# Kajtu_-DSP_user_interface.net
KiCad netlist of a schematic drawn in Altium Designer
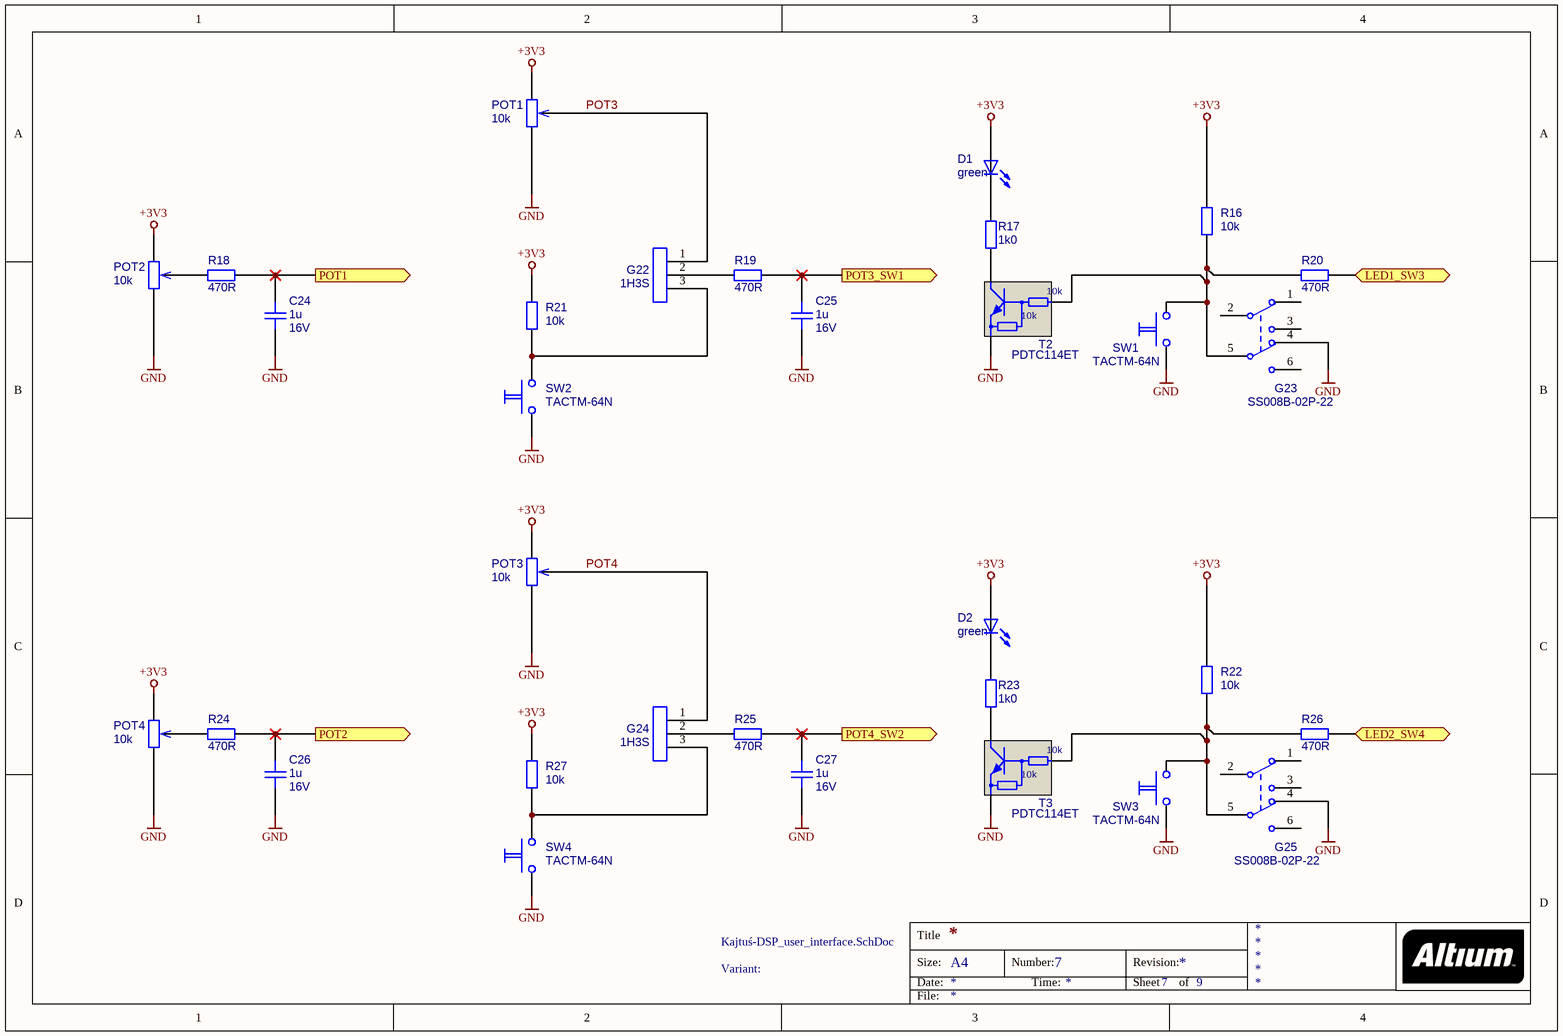
[diagram p0: Kajtuś-DSP_user_interface.SchDoc]

(export (version "E")
  (design (tool "Eeschema 10.0.6"))
  (components
    (comp (ref "C24")
      (value "1u")
      (footprint "C_0603_MA")
      (description "Kondensator ceramiczny SMD")
      (fields (field (name "PART NUMBER") "C_0603_1u_16V_X5R") (field (name "VOLTAGE") "16V"))
      (libsource (lib "AD_ostry_intlib") (part "C_0603_1u_16V_X5R"))
    )
    (comp (ref "C25")
      (value "1u")
      (footprint "C_0603_MA")
      (description "Kondensator ceramiczny SMD")
      (fields (field (name "PART NUMBER") "C_0603_1u_16V_X5R") (field (name "VOLTAGE") "16V"))
      (libsource (lib "AD_ostry_intlib") (part "C_0603_1u_16V_X5R"))
    )
    (comp (ref "C26")
      (value "1u")
      (footprint "C_0603_MA")
      (description "Kondensator ceramiczny SMD")
      (fields (field (name "PART NUMBER") "C_0603_1u_16V_X5R") (field (name "VOLTAGE") "16V"))
      (libsource (lib "AD_ostry_intlib") (part "C_0603_1u_16V_X5R"))
    )
    (comp (ref "C27")
      (value "1u")
      (footprint "C_0603_MA")
      (description "Kondensator ceramiczny SMD")
      (fields (field (name "PART NUMBER") "C_0603_1u_16V_X5R") (field (name "VOLTAGE") "16V"))
      (libsource (lib "AD_ostry_intlib") (part "C_0603_1u_16V_X5R"))
    )
    (comp (ref "D1")
      (value "green")
      (footprint "LED_0805_G")
      (description "Dioda LED SMD")
      (fields (field (name "PART NUMBER") "LED_SMD_generic") (field (name "MANUFACTURER") "??"))
      (libsource (lib "AD_ostry_intlib") (part "LED_SMD_generic"))
    )
    (comp (ref "D2")
      (value "green")
      (footprint "LED_0805_G")
      (description "Dioda LED SMD")
      (fields (field (name "PART NUMBER") "LED_SMD_generic") (field (name "MANUFACTURER") "??"))
      (libsource (lib "AD_ostry_intlib") (part "LED_SMD_generic"))
    )
    (comp (ref "G22")
      (value "1H3S")
      (footprint "1H3S_FHS")
      (description "Listwa jednorzędowa, 1x3 piny, raster 2,54mm")
      (fields (field (name "PART NUMBER") "G_1H3S") (field (name "MANUFACTURER") "generic"))
      (libsource (lib "AD_ostry_intlib") (part "G_1H3S"))
    )
    (comp (ref "G23")
      (value "SS008B-02P-22")
      (footprint "SW_DPDT_SS008B-02P-22")
      (description "Przełącznik suwakowy, DPTD")
      (fields
        (field (name "PART NUMBER") "SW_DPDT_SS008B-02P-22")
        (field (name "MANUFACTURER") "Canal Electronic")
      )
      (libsource (lib "AD_ostry_intlib") (part "SW_DPDT_SS008B-02P-22"))
    )
    (comp (ref "G24")
      (value "1H3S")
      (footprint "1H3S_FHS")
      (description "Listwa jednorzędowa, 1x3 piny, raster 2,54mm")
      (fields (field (name "PART NUMBER") "G_1H3S") (field (name "MANUFACTURER") "generic"))
      (libsource (lib "AD_ostry_intlib") (part "G_1H3S"))
    )
    (comp (ref "G25")
      (value "SS008B-02P-22")
      (footprint "SW_DPDT_SS008B-02P-22")
      (description "Przełącznik suwakowy, DPTD")
      (fields
        (field (name "PART NUMBER") "SW_DPDT_SS008B-02P-22")
        (field (name "MANUFACTURER") "Canal Electronic")
      )
      (libsource (lib "AD_ostry_intlib") (part "SW_DPDT_SS008B-02P-22"))
    )
    (comp (ref "POT1")
      (value "10k")
      (footprint "POT_BOURNS_3362P")
      (description "Potencjometr")
      (fields (field (name "PART NUMBER") "??") (field (name "MANUFACTURER") "bOURNS"))
      (libsource (lib "AD_ostry_intlib") (part "POT_10k_BOURNS_3362P"))
    )
    (comp (ref "POT2")
      (value "10k")
      (footprint "POT_BOURNS_3362P")
      (description "Potencjometr")
      (fields (field (name "PART NUMBER") "??") (field (name "MANUFACTURER") "bOURNS"))
      (libsource (lib "AD_ostry_intlib") (part "POT_10k_BOURNS_3362P"))
    )
    (comp (ref "POT3")
      (value "10k")
      (footprint "POT_BOURNS_3362P")
      (description "Potencjometr")
      (fields (field (name "PART NUMBER") "??") (field (name "MANUFACTURER") "bOURNS"))
      (libsource (lib "AD_ostry_intlib") (part "POT_10k_BOURNS_3362P"))
    )
    (comp (ref "POT4")
      (value "10k")
      (footprint "POT_BOURNS_3362P")
      (description "Potencjometr")
      (fields (field (name "PART NUMBER") "??") (field (name "MANUFACTURER") "bOURNS"))
      (libsource (lib "AD_ostry_intlib") (part "POT_10k_BOURNS_3362P"))
    )
    (comp (ref "R16")
      (value "10k")
      (footprint "R_0603_MA")
      (description "Rezystor SMD")
      (fields (field (name "MANUFACTURER") "Royal Ohm") (field (name "PART NUMBER") "R_0603_10k_5%"))
      (libsource (lib "AD_ostry_intlib") (part "R_0603_10k_5%"))
    )
    (comp (ref "R17")
      (value "1k0")
      (footprint "R_0603_MA")
      (description "Rezystor SMD")
      (fields (field (name "MANUFACTURER") "Royal Ohm") (field (name "PART NUMBER") "R_0603_1k0_5%"))
      (libsource (lib "AD_ostry_intlib") (part "R_0603_1k0_5%"))
    )
    (comp (ref "R18")
      (value "470R")
      (footprint "R_0603_MA")
      (description "Rezystor SMD")
      (fields (field (name "PART NUMBER") "R_0603_470R_5%") (field (name "MANUFACTURER") "Royal Ohm"))
      (libsource (lib "AD_ostry_intlib") (part "R_0603_470R_5%"))
    )
    (comp (ref "R19")
      (value "470R")
      (footprint "R_0603_MA")
      (description "Rezystor SMD")
      (fields (field (name "PART NUMBER") "R_0603_470R_5%") (field (name "MANUFACTURER") "Royal Ohm"))
      (libsource (lib "AD_ostry_intlib") (part "R_0603_470R_5%"))
    )
    (comp (ref "R20")
      (value "470R")
      (footprint "R_0603_MA")
      (description "Rezystor SMD")
      (fields (field (name "PART NUMBER") "R_0603_470R_5%") (field (name "MANUFACTURER") "Royal Ohm"))
      (libsource (lib "AD_ostry_intlib") (part "R_0603_470R_5%"))
    )
    (comp (ref "R21")
      (value "10k")
      (footprint "R_0603_MA")
      (description "Rezystor SMD")
      (fields (field (name "MANUFACTURER") "Royal Ohm") (field (name "PART NUMBER") "R_0603_10k_5%"))
      (libsource (lib "AD_ostry_intlib") (part "R_0603_10k_5%"))
    )
    (comp (ref "R22")
      (value "10k")
      (footprint "R_0603_MA")
      (description "Rezystor SMD")
      (fields (field (name "MANUFACTURER") "Royal Ohm") (field (name "PART NUMBER") "R_0603_10k_5%"))
      (libsource (lib "AD_ostry_intlib") (part "R_0603_10k_5%"))
    )
    (comp (ref "R23")
      (value "1k0")
      (footprint "R_0603_MA")
      (description "Rezystor SMD")
      (fields (field (name "MANUFACTURER") "Royal Ohm") (field (name "PART NUMBER") "R_0603_1k0_5%"))
      (libsource (lib "AD_ostry_intlib") (part "R_0603_1k0_5%"))
    )
    (comp (ref "R24")
      (value "470R")
      (footprint "R_0603_MA")
      (description "Rezystor SMD")
      (fields (field (name "PART NUMBER") "R_0603_470R_5%") (field (name "MANUFACTURER") "Royal Ohm"))
      (libsource (lib "AD_ostry_intlib") (part "R_0603_470R_5%"))
    )
    (comp (ref "R25")
      (value "470R")
      (footprint "R_0603_MA")
      (description "Rezystor SMD")
      (fields (field (name "PART NUMBER") "R_0603_470R_5%") (field (name "MANUFACTURER") "Royal Ohm"))
      (libsource (lib "AD_ostry_intlib") (part "R_0603_470R_5%"))
    )
    (comp (ref "R26")
      (value "470R")
      (footprint "R_0603_MA")
      (description "Rezystor SMD")
      (fields (field (name "PART NUMBER") "R_0603_470R_5%") (field (name "MANUFACTURER") "Royal Ohm"))
      (libsource (lib "AD_ostry_intlib") (part "R_0603_470R_5%"))
    )
    (comp (ref "R27")
      (value "10k")
      (footprint "R_0603_MA")
      (description "Rezystor SMD")
      (fields (field (name "MANUFACTURER") "Royal Ohm") (field (name "PART NUMBER") "R_0603_10k_5%"))
      (libsource (lib "AD_ostry_intlib") (part "R_0603_10k_5%"))
    )
    (comp (ref "SW1")
      (value "TACTM-64N")
      (footprint "SW_TACTM-64N")
      (description "Microswitch")
      (fields (field (name "PART NUMBER") "SW_TACTM-64N") (field (name "MANUFACTURER") "Ninigi"))
      (libsource (lib "AD_ostry_intlib") (part "SW_TACTM-64N"))
    )
    (comp (ref "SW2")
      (value "TACTM-64N")
      (footprint "SW_TACTM-64N")
      (description "Microswitch")
      (fields (field (name "PART NUMBER") "SW_TACTM-64N") (field (name "MANUFACTURER") "Ninigi"))
      (libsource (lib "AD_ostry_intlib") (part "SW_TACTM-64N"))
    )
    (comp (ref "SW3")
      (value "TACTM-64N")
      (footprint "SW_TACTM-64N")
      (description "Microswitch")
      (fields (field (name "PART NUMBER") "SW_TACTM-64N") (field (name "MANUFACTURER") "Ninigi"))
      (libsource (lib "AD_ostry_intlib") (part "SW_TACTM-64N"))
    )
    (comp (ref "SW4")
      (value "TACTM-64N")
      (footprint "SW_TACTM-64N")
      (description "Microswitch")
      (fields (field (name "PART NUMBER") "SW_TACTM-64N") (field (name "MANUFACTURER") "Ninigi"))
      (libsource (lib "AD_ostry_intlib") (part "SW_TACTM-64N"))
    )
    (comp (ref "T2")
      (value "PDTC114ET")
      (footprint "SOT-23")
      (description "NPN resistor-equipped transistor; R1=10k, R2=10k")
      (libsource (lib "MM_transistors") (part "T_SOT-23_PDTC114ET"))
    )
    (comp (ref "T3")
      (value "PDTC114ET")
      (footprint "SOT-23")
      (description "NPN resistor-equipped transistor; R1=10k, R2=10k")
      (libsource (lib "MM_transistors") (part "T_SOT-23_PDTC114ET"))
    )
  )
  (nets
    (net (code "1") (name "+3V3") (class "Default")
      (node (ref "D1") (pin "1") (pinfunction "A_1") (pintype "passive"))
      (node (ref "D2") (pin "1") (pinfunction "A_1") (pintype "passive"))
      (node (ref "POT1") (pin "1") (pinfunction "1_1") (pintype "passive"))
      (node (ref "POT2") (pin "1") (pinfunction "1_1") (pintype "passive"))
      (node (ref "POT3") (pin "1") (pinfunction "1_1") (pintype "passive"))
      (node (ref "POT4") (pin "1") (pinfunction "1_1") (pintype "passive"))
      (node (ref "R16") (pin "1") (pinfunction "1_1") (pintype "passive"))
      (node (ref "R21") (pin "1") (pinfunction "1_1") (pintype "passive"))
      (node (ref "R22") (pin "1") (pinfunction "1_1") (pintype "passive"))
      (node (ref "R27") (pin "1") (pinfunction "1_1") (pintype "passive"))
    )
    (net (code "2") (name "/LED1_SW3") (class "Default")
      (node (ref "R20") (pin "2") (pinfunction "2_2") (pintype "passive"))
    )
    (net (code "3") (name "/LED2_SW4") (class "Default")
      (node (ref "R26") (pin "2") (pinfunction "2_2") (pintype "passive"))
    )
    (net (code "4") (name "/POT1") (class "Default")
      (node (ref "C24") (pin "1") (pinfunction "1_1") (pintype "passive"))
      (node (ref "R18") (pin "2") (pinfunction "2_2") (pintype "passive"))
    )
    (net (code "5") (name "/POT2") (class "Default")
      (node (ref "C26") (pin "1") (pinfunction "1_1") (pintype "passive"))
      (node (ref "R24") (pin "2") (pinfunction "2_2") (pintype "passive"))
    )
    (net (code "6") (name "/POT3") (class "Default")
      (node (ref "G22") (pin "1") (pinfunction "1_1") (pintype "passive"))
      (node (ref "POT1") (pin "2") (pinfunction "2_2") (pintype "passive"))
    )
    (net (code "7") (name "/POT3_SW1") (class "Default")
      (node (ref "C25") (pin "1") (pinfunction "1_1") (pintype "passive"))
      (node (ref "R19") (pin "2") (pinfunction "2_2") (pintype "passive"))
    )
    (net (code "8") (name "/POT4") (class "Default")
      (node (ref "G24") (pin "1") (pinfunction "1_1") (pintype "passive"))
      (node (ref "POT3") (pin "2") (pinfunction "2_2") (pintype "passive"))
    )
    (net (code "9") (name "/POT4_SW2") (class "Default")
      (node (ref "C27") (pin "1") (pinfunction "1_1") (pintype "passive"))
      (node (ref "R25") (pin "2") (pinfunction "2_2") (pintype "passive"))
    )
    (net (code "10") (name "GND") (class "Default")
      (node (ref "C24") (pin "2") (pinfunction "2_2") (pintype "passive"))
      (node (ref "C25") (pin "2") (pinfunction "2_2") (pintype "passive"))
      (node (ref "C26") (pin "2") (pinfunction "2_2") (pintype "passive"))
      (node (ref "C27") (pin "2") (pinfunction "2_2") (pintype "passive"))
      (node (ref "G23") (pin "4") (pinfunction "NC2_4") (pintype "passive"))
      (node (ref "G25") (pin "4") (pinfunction "NC2_4") (pintype "passive"))
      (node (ref "POT1") (pin "3") (pinfunction "3_3") (pintype "passive"))
      (node (ref "POT2") (pin "3") (pinfunction "3_3") (pintype "passive"))
      (node (ref "POT3") (pin "3") (pinfunction "3_3") (pintype "passive"))
      (node (ref "POT4") (pin "3") (pinfunction "3_3") (pintype "passive"))
      (node (ref "SW1") (pin "1") (pinfunction "1_1") (pintype "passive"))
      (node (ref "SW2") (pin "1") (pinfunction "1_1") (pintype "passive"))
      (node (ref "SW3") (pin "1") (pinfunction "1_1") (pintype "passive"))
      (node (ref "SW4") (pin "1") (pinfunction "1_1") (pintype "passive"))
      (node (ref "T2") (pin "2") (pinfunction "E_2") (pintype "passive"))
      (node (ref "T3") (pin "2") (pinfunction "E_2") (pintype "passive"))
    )
    (net (code "11") (name "Net-(D1-K)") (class "Default")
      (node (ref "D1") (pin "2") (pinfunction "K_2") (pintype "passive"))
      (node (ref "R17") (pin "1") (pinfunction "1_1") (pintype "passive"))
    )
    (net (code "12") (name "Net-(D2-K)") (class "Default")
      (node (ref "D2") (pin "2") (pinfunction "K_2") (pintype "passive"))
      (node (ref "R23") (pin "1") (pinfunction "1_1") (pintype "passive"))
    )
    (net (code "13") (name "Net-(G22-Pad2)") (class "Default")
      (node (ref "G22") (pin "2") (pinfunction "2_2") (pintype "passive"))
      (node (ref "R19") (pin "1") (pinfunction "1_1") (pintype "passive"))
    )
    (net (code "14") (name "Net-(G22-Pad3)") (class "Default")
      (node (ref "G22") (pin "3") (pinfunction "3_3") (pintype "passive"))
      (node (ref "R21") (pin "2") (pinfunction "2_2") (pintype "passive"))
      (node (ref "SW2") (pin "4") (pinfunction "4_4") (pintype "passive"))
    )
    (net (code "15") (name "Net-(G23-COM2)") (class "Default")
      (node (ref "G23") (pin "5") (pinfunction "COM2_5") (pintype "passive"))
      (node (ref "R16") (pin "2") (pinfunction "2_2") (pintype "passive"))
      (node (ref "R20") (pin "1") (pinfunction "1_1") (pintype "passive"))
      (node (ref "SW1") (pin "4") (pinfunction "4_4") (pintype "passive"))
      (node (ref "T2") (pin "1") (pinfunction "B_1") (pintype "passive"))
    )
    (net (code "16") (name "Net-(G24-Pad2)") (class "Default")
      (node (ref "G24") (pin "2") (pinfunction "2_2") (pintype "passive"))
      (node (ref "R25") (pin "1") (pinfunction "1_1") (pintype "passive"))
    )
    (net (code "17") (name "Net-(G24-Pad3)") (class "Default")
      (node (ref "G24") (pin "3") (pinfunction "3_3") (pintype "passive"))
      (node (ref "R27") (pin "2") (pinfunction "2_2") (pintype "passive"))
      (node (ref "SW4") (pin "4") (pinfunction "4_4") (pintype "passive"))
    )
    (net (code "18") (name "Net-(G25-COM2)") (class "Default")
      (node (ref "G25") (pin "5") (pinfunction "COM2_5") (pintype "passive"))
      (node (ref "R22") (pin "2") (pinfunction "2_2") (pintype "passive"))
      (node (ref "R26") (pin "1") (pinfunction "1_1") (pintype "passive"))
      (node (ref "SW3") (pin "4") (pinfunction "4_4") (pintype "passive"))
      (node (ref "T3") (pin "1") (pinfunction "B_1") (pintype "passive"))
    )
    (net (code "19") (name "Net-(POT2-Pad2)") (class "Default")
      (node (ref "POT2") (pin "2") (pinfunction "2_2") (pintype "passive"))
      (node (ref "R18") (pin "1") (pinfunction "1_1") (pintype "passive"))
    )
    (net (code "20") (name "Net-(POT4-Pad2)") (class "Default")
      (node (ref "POT4") (pin "2") (pinfunction "2_2") (pintype "passive"))
      (node (ref "R24") (pin "1") (pinfunction "1_1") (pintype "passive"))
    )
    (net (code "21") (name "Net-(T2-C)") (class "Default")
      (node (ref "R17") (pin "2") (pinfunction "2_2") (pintype "passive"))
      (node (ref "T2") (pin "3") (pinfunction "C_3") (pintype "passive"))
    )
    (net (code "22") (name "Net-(T3-C)") (class "Default")
      (node (ref "R23") (pin "2") (pinfunction "2_2") (pintype "passive"))
      (node (ref "T3") (pin "3") (pinfunction "C_3") (pintype "passive"))
    )
    (net (code "23") (name "unconnected-(G23-COM1-Pad2)") (class "Default")
      (node (ref "G23") (pin "2") (pinfunction "COM1_2") (pintype "passive"))
    )
    (net (code "24") (name "unconnected-(G23-NC1-Pad1)") (class "Default")
      (node (ref "G23") (pin "1") (pinfunction "NC1_1") (pintype "passive"))
    )
    (net (code "25") (name "unconnected-(G23-NO1-Pad3)") (class "Default")
      (node (ref "G23") (pin "3") (pinfunction "NO1_3") (pintype "passive"))
    )
    (net (code "26") (name "unconnected-(G23-NO2-Pad6)") (class "Default")
      (node (ref "G23") (pin "6") (pinfunction "NO2_6") (pintype "passive"))
    )
    (net (code "27") (name "unconnected-(G25-COM1-Pad2)") (class "Default")
      (node (ref "G25") (pin "2") (pinfunction "COM1_2") (pintype "passive"))
    )
    (net (code "28") (name "unconnected-(G25-NC1-Pad1)") (class "Default")
      (node (ref "G25") (pin "1") (pinfunction "NC1_1") (pintype "passive"))
    )
    (net (code "29") (name "unconnected-(G25-NO1-Pad3)") (class "Default")
      (node (ref "G25") (pin "3") (pinfunction "NO1_3") (pintype "passive"))
    )
    (net (code "30") (name "unconnected-(G25-NO2-Pad6)") (class "Default")
      (node (ref "G25") (pin "6") (pinfunction "NO2_6") (pintype "passive"))
    )
  )
)
